# voeding.net
KiCad netlist of a schematic drawn in Altium Designer
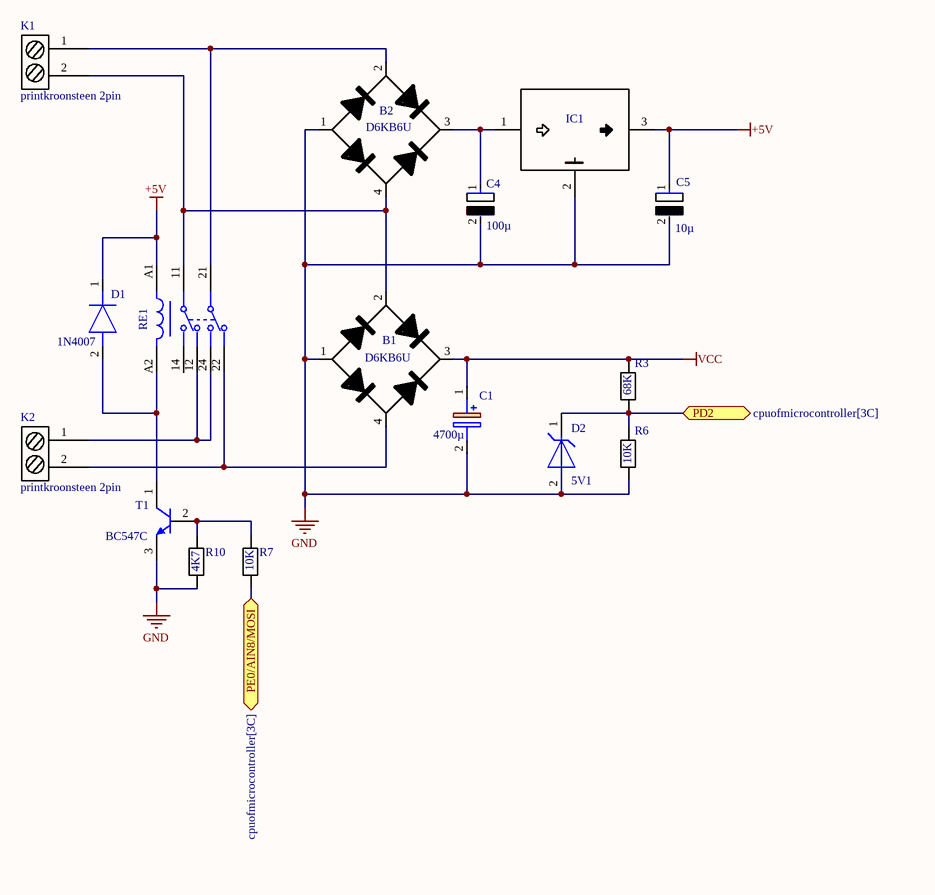
[diagram p0: voeding.SchDoc]

(export (version "E")
  (design (tool "Eeschema 10.0.6"))
  (components
    (comp (ref "B1") (value "D6KB6U") (footprint "D6KB6U") (libsource (lib "Schlib1") (part "D6KB6U")))
    (comp (ref "B2") (value "D6KB6U") (footprint "D6KB6U") (libsource (lib "Schlib1") (part "D6KB6U")))
    (comp (ref "C1")
      (value "4700µ")
      (footprint "CAPPRD1000W80D2200H3700")
      (description "Capacitor Polarised")
      (fields
        (field (name "MANUFACTURER_PART_NUMBER") "ESK478M050AQ3AA")
        (field (name "MOUSER PART NUMBER") "80-ESK478M050AQ3AA")
      )
      (libsource (lib "Schlib1") (part "CondensatorGroot"))
    )
    (comp (ref "C4")
      (value "100µ")
      (footprint "100uF/50v aluminum electrolytic capacitor")
      (description "CAP CER 0.1UF 10V X5R 0402")
      (fields (field (name "MANUFACTURER") "Kemet") (field (name "TOLERANCE") "0.1"))
      (libsource (lib "Schlib1") (part "Capacitor"))
    )
    (comp (ref "C5")
      (value "10µ")
      (footprint "RESC2013X50X30LL20T20")
      (description "CAP CER 0.1UF 10V X5R 0402")
      (fields (field (name "MANUFACTURER") "Kemet") (field (name "TOLERANCE") "0.1"))
      (libsource (lib "Schlib1") (part "Capacitor"))
    )
    (comp (ref "D1")
      (value "1N4007")
      (footprint "DIOAD1405W86L465D235")
      (description "Diode")
      (fields
        (field (name "MANUFACTURER_PART_NUMBER") "1N4007-E3/73")
        (field (name "MOUSER PART NUMBER") "625-1N4007-E3/73")
      )
      (libsource (lib "Schlib1") (part "1N4007-E3_73"))
    )
    (comp (ref "D2")
      (value "5V1")
      (footprint "FP-SOD123-IPC_A")
      (description "DIODE ZENER 5.1V 500MW SOD123")
      (fields
        (field (name "MANUFACTURER PART NUMBER") "BZT52C5V1-7-F")
        (field (name "OCTOPART") "https://octopart.com/bzt52c5v1-7-f-diodes+inc.-326718")
      )
      (libsource (lib "Schlib1") (part "Zenerdiode"))
    )
    (comp (ref "IC1")
      (value "~")
      (footprint "MURA-OKI-78SR-3")
      (description "Non-Isolated DC/DC Converter, 7.5 W, 7 to 36 V, 1.5 A, -40 to 85 degC, 3-Pin THD, RoHS")
      (fields (field (name "MANUFACTURER") "Murata"))
      (libsource (lib "Schlib1") (part "OKI-78SR-5/1.5-W36-C"))
    )
    (comp (ref "K1")
      (value "printkroonsteen 2pin")
      (footprint "printkroonsteen 2pin")
      (libsource (lib "Schlib1") (part "printkroonsteen 2pin"))
    )
    (comp (ref "K2")
      (value "printkroonsteen 2pin")
      (footprint "printkroonsteen 2pin")
      (libsource (lib "Schlib1") (part "printkroonsteen 2pin"))
    )
    (comp (ref "R3")
      (value "68K")
      (footprint "RESC2013X50X30LL20T20")
      (fields (field (name "MANUFACTURER") "Vishay Dale") (field (name "PART NUMBER") "CRCW08050000Z0EA"))
      (libsource (lib "Schlib1") (part "weerstand"))
    )
    (comp (ref "R6")
      (value "10K")
      (footprint "RESC2013X50X30LL20T20")
      (fields (field (name "MANUFACTURER") "Vishay Dale") (field (name "PART NUMBER") "CRCW08050000Z0EA"))
      (libsource (lib "Schlib1") (part "weerstand"))
    )
    (comp (ref "R7")
      (value "10K")
      (footprint "RESC2013X50X30LL20T20")
      (fields (field (name "MANUFACTURER") "Vishay Dale") (field (name "PART NUMBER") "CRCW08050000Z0EA"))
      (libsource (lib "Schlib1") (part "weerstand"))
    )
    (comp (ref "R10")
      (value "4K7")
      (footprint "RESC2013X50X30LL20T20")
      (fields (field (name "MANUFACTURER") "Vishay Dale") (field (name "PART NUMBER") "CRCW08050000Z0EA"))
      (libsource (lib "Schlib1") (part "weerstand"))
    )
    (comp (ref "RE1")
      (value "~")
      (footprint "FP-RT424005-MFG")
      (description "RELAY GENERAL PURPOSE DPDT 8A 5V")
      (fields
        (field (name "MANUFACTURER PART NUMBER") "RT424005")
        (field (name "OCTOPART") "https://octopart.com/5-1393243-9-te+connectivity-41835766")
      )
      (libsource (lib "Schlib1") (part "RT424005"))
    )
    (comp (ref "T1")
      (value "BC547C")
      (footprint "ONSC-TO-92-3-29-11")
      (description "Amplifier Transistor, NPN Silicon, 3-Pin TO-92, Bulk Box")
      (fields (field (name "MANUFACTURER") "On Semiconductor"))
      (libsource (lib "Schlib1") (part "BC547C"))
    )
  )
  (nets
    (net (code "1") (name "+5V") (class "Default")
      (node (ref "C5") (pin "1") (pinfunction "1_1") (pintype "passive"))
      (node (ref "D1") (pin "1") (pinfunction "K_1") (pintype "passive"))
      (node (ref "IC1") (pin "3") (pintype "power_in"))
      (node (ref "RE1") (pin "A1") (pinfunction "A1_A1") (pintype "passive"))
    )
    (net (code "2") (name "/PD2") (class "Default")
      (node (ref "D2") (pin "1") (pinfunction "C_1") (pintype "passive"))
      (node (ref "R3") (pin "1") (pinfunction "1_1") (pintype "passive"))
      (node (ref "R6") (pin "2") (pinfunction "2_2") (pintype "passive"))
    )
    (net (code "3") (name "/PE0{slash}AIN8{slash}MOSI") (class "Default")
      (node (ref "R7") (pin "1") (pinfunction "1_1") (pintype "passive"))
    )
    (net (code "4") (name "GND") (class "Default")
      (node (ref "B1") (pin "1") (pintype "passive"))
      (node (ref "B2") (pin "1") (pintype "passive"))
      (node (ref "C1") (pin "2") (pinfunction "-_2") (pintype "passive"))
      (node (ref "C4") (pin "2") (pinfunction "2_2") (pintype "passive"))
      (node (ref "C5") (pin "2") (pinfunction "2_2") (pintype "passive"))
      (node (ref "D2") (pin "2") (pinfunction "A_2") (pintype "passive"))
      (node (ref "IC1") (pin "2") (pinfunction "COMMON_2") (pintype "power_in"))
      (node (ref "R10") (pin "1") (pinfunction "1_1") (pintype "passive"))
      (node (ref "R6") (pin "1") (pinfunction "1_1") (pintype "passive"))
      (node (ref "T1") (pin "3") (pinfunction "E_3") (pintype "passive"))
    )
    (net (code "5") (name "Net-(B1-Pad2)") (class "Default")
      (node (ref "B1") (pin "2") (pintype "passive"))
      (node (ref "B2") (pin "4") (pintype "passive"))
      (node (ref "K1") (pin "2") (pintype "passive"))
      (node (ref "RE1") (pin "11") (pinfunction "11_11") (pintype "passive"))
    )
    (net (code "6") (name "Net-(B1-Pad4)") (class "Default")
      (node (ref "B1") (pin "4") (pintype "passive"))
      (node (ref "K2") (pin "2") (pintype "passive"))
      (node (ref "RE1") (pin "22") (pinfunction "22_22") (pintype "passive"))
    )
    (net (code "7") (name "Net-(B2-Pad2)") (class "Default")
      (node (ref "B2") (pin "2") (pintype "passive"))
      (node (ref "K1") (pin "1") (pintype "passive"))
      (node (ref "RE1") (pin "21") (pinfunction "21_21") (pintype "passive"))
    )
    (net (code "8") (name "Net-(B2-Pad3)") (class "Default")
      (node (ref "B2") (pin "3") (pintype "passive"))
      (node (ref "C4") (pin "1") (pinfunction "1_1") (pintype "passive"))
      (node (ref "IC1") (pin "1") (pintype "power_in"))
    )
    (net (code "9") (name "Net-(D1-A)") (class "Default")
      (node (ref "D1") (pin "2") (pinfunction "A_2") (pintype "passive"))
      (node (ref "RE1") (pin "A2") (pinfunction "A2_A2") (pintype "passive"))
      (node (ref "T1") (pin "1") (pinfunction "C_1") (pintype "passive"))
    )
    (net (code "10") (name "Net-(K2-Pad1)") (class "Default")
      (node (ref "K2") (pin "1") (pintype "passive"))
      (node (ref "RE1") (pin "12") (pinfunction "12_12") (pintype "passive"))
      (node (ref "RE1") (pin "24") (pinfunction "24_24") (pintype "passive"))
    )
    (net (code "11") (name "Net-(T1-B)") (class "Default")
      (node (ref "R10") (pin "2") (pinfunction "2_2") (pintype "passive"))
      (node (ref "R7") (pin "2") (pinfunction "2_2") (pintype "passive"))
      (node (ref "T1") (pin "2") (pinfunction "B_2") (pintype "passive"))
    )
    (net (code "12") (name "VCC") (class "Default")
      (node (ref "B1") (pin "3") (pintype "passive"))
      (node (ref "C1") (pin "1") (pinfunction "+_1") (pintype "passive"))
      (node (ref "R3") (pin "2") (pinfunction "2_2") (pintype "passive"))
    )
    (net (code "13") (name "unconnected-(RE1-Pad14)") (class "Default")
      (node (ref "RE1") (pin "14") (pinfunction "14_14") (pintype "passive"))
    )
  )
)
